# p0a-001.net
KiCad netlist of a schematic drawn in EAGLE
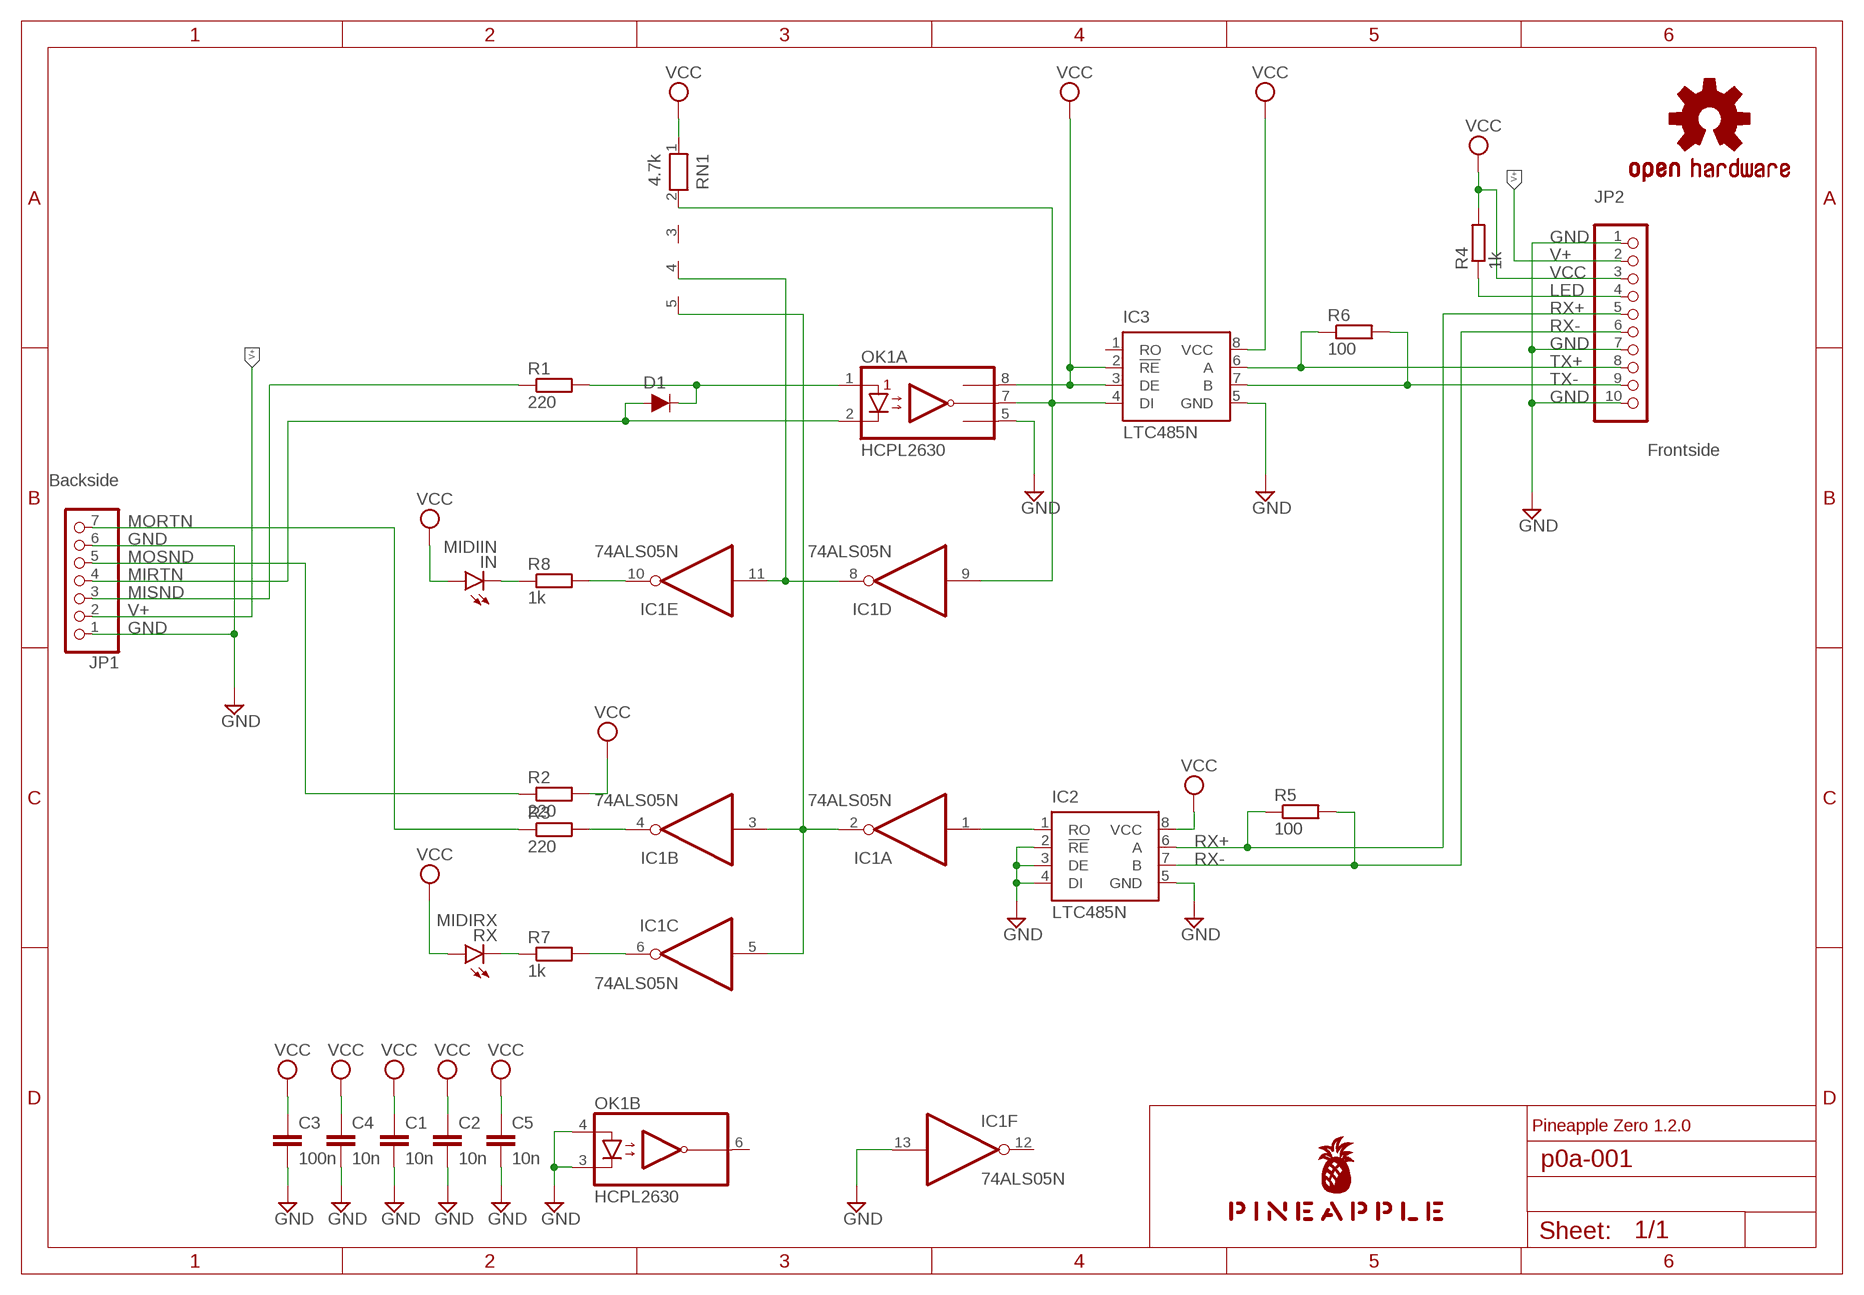
[diagram p0: schematic, sheet 1]

(export (version "E")
  (design (tool "Eeschema 10.0.6"))
  (components
    (comp (ref "C1")
      (value "10n")
      (footprint "eagle-import:C025-024X044")
      (libsource (lib "eagle-import") (part "C-EU025-024X044"))
    )
    (comp (ref "C2")
      (value "10n")
      (footprint "eagle-import:C025-024X044")
      (libsource (lib "eagle-import") (part "C-EU025-024X044"))
    )
    (comp (ref "C3")
      (value "100n")
      (footprint "eagle-import:C025-024X044")
      (libsource (lib "eagle-import") (part "C-EU025-024X044"))
    )
    (comp (ref "C4")
      (value "10n")
      (footprint "eagle-import:C025-024X044")
      (libsource (lib "eagle-import") (part "C-EU025-024X044"))
    )
    (comp (ref "C5")
      (value "10n")
      (footprint "eagle-import:C025-024X044")
      (libsource (lib "eagle-import") (part "C-EU025-024X044"))
    )
    (comp (ref "D1")
      (value "DIODE-1N4148")
      (footprint "eagle-import:DIODE-1N4148")
      (libsource (lib "eagle-import") (part "DIODE-1N4148"))
    )
    (comp (ref "IC1")
      (value "74ALS05N")
      (footprint "eagle-import:DIL14")
      (libsource (lib "eagle-import") (part "7405NALS"))
    )
    (comp (ref "IC2")
      (value "LTC485N")
      (footprint "eagle-import:DIL08")
      (libsource (lib "eagle-import") (part "LTC485N"))
    )
    (comp (ref "IC3")
      (value "LTC485N")
      (footprint "eagle-import:DIL08")
      (libsource (lib "eagle-import") (part "LTC485N"))
    )
    (comp (ref "IN")
      (value "MIDIIN")
      (footprint "eagle-import:Q62902-B152")
      (libsource (lib "eagle-import") (part "LEDB152"))
    )
    (comp (ref "JP1")
      (value "Backside")
      (footprint "eagle-import:1X07")
      (libsource (lib "eagle-import") (part "PINHD-1X7"))
    )
    (comp (ref "JP2")
      (value "Frontside")
      (footprint "eagle-import:1X10")
      (libsource (lib "eagle-import") (part "PINHD-1X10"))
    )
    (comp (ref "LOGO1")
      (value "OSHW-LOGOS-COPPER")
      (footprint "eagle-import:OSHW-LOGO-S_COPPER")
      (libsource (lib "eagle-import") (part "OSHW-LOGOS-COPPER"))
    )
    (comp (ref "OK1")
      (value "HCPL2630")
      (footprint "eagle-import:DIL08")
      (fields (field (name "MF") "AGILENT TECHNOLOGIES") (field (name "MPN") "HCPL-2630-000E"))
      (libsource (lib "eagle-import") (part "HCPL2630"))
    )
    (comp (ref "R1")
      (value "220")
      (footprint "eagle-import:0204_5")
      (libsource (lib "eagle-import") (part "R-EU_0204/5"))
    )
    (comp (ref "R2")
      (value "220")
      (footprint "eagle-import:0204_5")
      (libsource (lib "eagle-import") (part "R-EU_0204/5"))
    )
    (comp (ref "R3")
      (value "220")
      (footprint "eagle-import:0204_5")
      (libsource (lib "eagle-import") (part "R-EU_0204/5"))
    )
    (comp (ref "R4")
      (value "1k")
      (footprint "eagle-import:0204_5")
      (libsource (lib "eagle-import") (part "R-EU_0204/5"))
    )
    (comp (ref "R5")
      (value "100")
      (footprint "eagle-import:0204_5")
      (libsource (lib "eagle-import") (part "R-EU_0204/5"))
    )
    (comp (ref "R6")
      (value "100")
      (footprint "eagle-import:0204_5")
      (libsource (lib "eagle-import") (part "R-EU_0204/5"))
    )
    (comp (ref "R7")
      (value "1k")
      (footprint "eagle-import:0204_5")
      (libsource (lib "eagle-import") (part "R-EU_0204/5"))
    )
    (comp (ref "R8")
      (value "1k")
      (footprint "eagle-import:0204_5")
      (libsource (lib "eagle-import") (part "R-EU_0204/5"))
    )
    (comp (ref "RN1")
      (value "4.7k")
      (footprint "eagle-import:RN-5")
      (libsource (lib "eagle-import") (part "RN04"))
    )
    (comp (ref "RX")
      (value "MIDIRX")
      (footprint "eagle-import:Q62902-B152")
      (libsource (lib "eagle-import") (part "LEDB152"))
    )
    (comp (ref "U$1")
      (value "PINEAPPLE450")
      (footprint "eagle-import:PINEAPPLE450")
      (libsource (lib "eagle-import") (part "PINEAPPLE450"))
    )
  )
  (nets
    (net (code "1") (name "/LED") (class "Default")
      (node (ref "JP2") (pin "4") (pinfunction "4_4") (pintype "passive"))
      (node (ref "R4") (pin "1") (pinfunction "1_1") (pintype "passive"))
    )
    (net (code "2") (name "/MIRTN") (class "Default")
      (node (ref "D1") (pin "A") (pinfunction "A_A") (pintype "passive"))
      (node (ref "JP1") (pin "4") (pinfunction "4_4") (pintype "passive"))
      (node (ref "OK1") (pin "2") (pinfunction "C1_2") (pintype "passive"))
    )
    (net (code "3") (name "/MISND") (class "Default")
      (node (ref "JP1") (pin "3") (pinfunction "3_3") (pintype "passive"))
      (node (ref "R1") (pin "1") (pinfunction "1_1") (pintype "passive"))
    )
    (net (code "4") (name "/MORTN") (class "Default")
      (node (ref "JP1") (pin "7") (pinfunction "7_7") (pintype "passive"))
      (node (ref "R3") (pin "1") (pinfunction "1_1") (pintype "passive"))
    )
    (net (code "5") (name "/MOSND") (class "Default")
      (node (ref "JP1") (pin "5") (pinfunction "5_5") (pintype "passive"))
      (node (ref "R2") (pin "1") (pinfunction "1_1") (pintype "passive"))
    )
    (net (code "6") (name "/RX+") (class "Default")
      (node (ref "IC2") (pin "6") (pinfunction "A_6") (pintype "bidirectional"))
      (node (ref "JP2") (pin "5") (pinfunction "5_5") (pintype "passive"))
      (node (ref "R5") (pin "1") (pinfunction "1_1") (pintype "passive"))
    )
    (net (code "7") (name "/RX-") (class "Default")
      (node (ref "IC2") (pin "7") (pinfunction "B_7") (pintype "bidirectional"))
      (node (ref "JP2") (pin "6") (pinfunction "6_6") (pintype "passive"))
      (node (ref "R5") (pin "2") (pinfunction "2_2") (pintype "passive"))
    )
    (net (code "8") (name "/TX+") (class "Default")
      (node (ref "IC3") (pin "6") (pinfunction "A_6") (pintype "bidirectional"))
      (node (ref "JP2") (pin "8") (pinfunction "8_8") (pintype "passive"))
      (node (ref "R6") (pin "1") (pinfunction "1_1") (pintype "passive"))
    )
    (net (code "9") (name "/TX-") (class "Default")
      (node (ref "IC3") (pin "7") (pinfunction "B_7") (pintype "bidirectional"))
      (node (ref "JP2") (pin "9") (pinfunction "9_9") (pintype "passive"))
      (node (ref "R6") (pin "2") (pinfunction "2_2") (pintype "passive"))
    )
    (net (code "10") (name "GND") (class "Default")
      (node (ref "C1") (pin "2") (pinfunction "2_2") (pintype "passive"))
      (node (ref "C2") (pin "2") (pinfunction "2_2") (pintype "passive"))
      (node (ref "C3") (pin "2") (pinfunction "2_2") (pintype "passive"))
      (node (ref "C4") (pin "2") (pinfunction "2_2") (pintype "passive"))
      (node (ref "C5") (pin "2") (pinfunction "2_2") (pintype "passive"))
      (node (ref "IC1") (pin "13") (pinfunction "I_13") (pintype "input"))
      (node (ref "IC2") (pin "2") (pinfunction "~{RE}_2") (pintype "input"))
      (node (ref "IC2") (pin "3") (pinfunction "DE_3") (pintype "input"))
      (node (ref "IC2") (pin "4") (pinfunction "DI_4") (pintype "input"))
      (node (ref "IC2") (pin "5") (pinfunction "GND_5") (pintype "input"))
      (node (ref "IC3") (pin "5") (pinfunction "GND_5") (pintype "input"))
      (node (ref "JP1") (pin "1") (pinfunction "1_1") (pintype "passive"))
      (node (ref "JP1") (pin "6") (pinfunction "6_6") (pintype "passive"))
      (node (ref "JP2") (pin "1") (pinfunction "1_1") (pintype "passive"))
      (node (ref "JP2") (pin "10") (pinfunction "10_10") (pintype "passive"))
      (node (ref "JP2") (pin "7") (pinfunction "7_7") (pintype "passive"))
      (node (ref "OK1") (pin "3") (pinfunction "C2_3") (pintype "passive"))
      (node (ref "OK1") (pin "4") (pinfunction "A2_4") (pintype "passive"))
      (node (ref "OK1") (pin "5") (pinfunction "GND_5") (pintype "passive"))
    )
    (net (code "11") (name "Net-(IC1A-I)") (class "Default")
      (node (ref "IC1") (pin "1") (pinfunction "I_1") (pintype "input"))
      (node (ref "IC2") (pin "1") (pinfunction "RO_1") (pintype "output"))
    )
    (net (code "12") (name "Net-(IC1A-O)") (class "Default")
      (node (ref "IC1") (pin "2") (pinfunction "O_2") (pintype "open_collector"))
      (node (ref "IC1") (pin "3") (pinfunction "I_3") (pintype "input"))
      (node (ref "IC1") (pin "5") (pinfunction "I_5") (pintype "input"))
      (node (ref "RN1") (pin "5") (pinfunction "5_5") (pintype "passive"))
    )
    (net (code "13") (name "Net-(IC1B-O)") (class "Default")
      (node (ref "IC1") (pin "4") (pinfunction "O_4") (pintype "open_collector"))
      (node (ref "R3") (pin "2") (pinfunction "2_2") (pintype "passive"))
    )
    (net (code "14") (name "Net-(IC1C-O)") (class "Default")
      (node (ref "IC1") (pin "6") (pinfunction "O_6") (pintype "open_collector"))
      (node (ref "R7") (pin "2") (pinfunction "2_2") (pintype "passive"))
    )
    (net (code "15") (name "Net-(IC1D-I)") (class "Default")
      (node (ref "IC1") (pin "9") (pinfunction "I_9") (pintype "input"))
      (node (ref "IC3") (pin "4") (pinfunction "DI_4") (pintype "input"))
      (node (ref "OK1") (pin "7") (pinfunction "VO1_7") (pintype "passive"))
      (node (ref "RN1") (pin "2") (pinfunction "2_2") (pintype "passive"))
    )
    (net (code "16") (name "Net-(IC1D-O)") (class "Default")
      (node (ref "IC1") (pin "11") (pinfunction "I_11") (pintype "input"))
      (node (ref "IC1") (pin "8") (pinfunction "O_8") (pintype "open_collector"))
      (node (ref "RN1") (pin "4") (pinfunction "4_4") (pintype "passive"))
    )
    (net (code "17") (name "Net-(IC1E-O)") (class "Default")
      (node (ref "IC1") (pin "10") (pinfunction "O_10") (pintype "open_collector"))
      (node (ref "R8") (pin "2") (pinfunction "2_2") (pintype "passive"))
    )
    (net (code "18") (name "Net-(IN-C)") (class "Default")
      (node (ref "IN") (pin "K") (pinfunction "C_K") (pintype "passive"))
      (node (ref "R8") (pin "1") (pinfunction "1_1") (pintype "passive"))
    )
    (net (code "19") (name "Net-(OK1A-A1)") (class "Default")
      (node (ref "D1") (pin "C") (pinfunction "C_C") (pintype "passive"))
      (node (ref "OK1") (pin "1") (pinfunction "A1_1") (pintype "passive"))
      (node (ref "R1") (pin "2") (pinfunction "2_2") (pintype "passive"))
    )
    (net (code "20") (name "Net-(RX-C)") (class "Default")
      (node (ref "R7") (pin "1") (pinfunction "1_1") (pintype "passive"))
      (node (ref "RX") (pin "K") (pinfunction "C_K") (pintype "passive"))
    )
    (net (code "21") (name "V+") (class "Default")
      (node (ref "JP1") (pin "2") (pinfunction "2_2") (pintype "passive"))
      (node (ref "JP2") (pin "2") (pinfunction "2_2") (pintype "passive"))
    )
    (net (code "22") (name "VCC") (class "Default")
      (node (ref "C1") (pin "1") (pinfunction "1_1") (pintype "passive"))
      (node (ref "C2") (pin "1") (pinfunction "1_1") (pintype "passive"))
      (node (ref "C3") (pin "1") (pinfunction "1_1") (pintype "passive"))
      (node (ref "C4") (pin "1") (pinfunction "1_1") (pintype "passive"))
      (node (ref "C5") (pin "1") (pinfunction "1_1") (pintype "passive"))
      (node (ref "IC2") (pin "8") (pinfunction "VCC_8") (pintype "input"))
      (node (ref "IC3") (pin "2") (pinfunction "~{RE}_2") (pintype "input"))
      (node (ref "IC3") (pin "3") (pinfunction "DE_3") (pintype "input"))
      (node (ref "IC3") (pin "8") (pinfunction "VCC_8") (pintype "input"))
      (node (ref "IN") (pin "A") (pinfunction "A_A") (pintype "passive"))
      (node (ref "JP2") (pin "3") (pinfunction "3_3") (pintype "passive"))
      (node (ref "OK1") (pin "8") (pinfunction "VCC_8") (pintype "passive"))
      (node (ref "R2") (pin "2") (pinfunction "2_2") (pintype "passive"))
      (node (ref "R4") (pin "2") (pinfunction "2_2") (pintype "passive"))
      (node (ref "RN1") (pin "1") (pinfunction "1_1") (pintype "passive"))
      (node (ref "RX") (pin "A") (pinfunction "A_A") (pintype "passive"))
    )
    (net (code "23") (name "unconnected-(IC1F-O-Pad12)") (class "Default")
      (node (ref "IC1") (pin "12") (pinfunction "O_12") (pintype "open_collector"))
    )
    (net (code "24") (name "unconnected-(IC3-RO-Pad1)") (class "Default")
      (node (ref "IC3") (pin "1") (pinfunction "RO_1") (pintype "output"))
    )
    (net (code "25") (name "unconnected-(OK1B-VO2-Pad6)") (class "Default")
      (node (ref "OK1") (pin "6") (pinfunction "VO2_6") (pintype "passive"))
    )
    (net (code "26") (name "unconnected-(RN1-Pad3)") (class "Default")
      (node (ref "RN1") (pin "3") (pinfunction "3_3") (pintype "passive"))
    )
  )
)
